# vga3.net
KiCad netlist of a schematic drawn in EAGLE
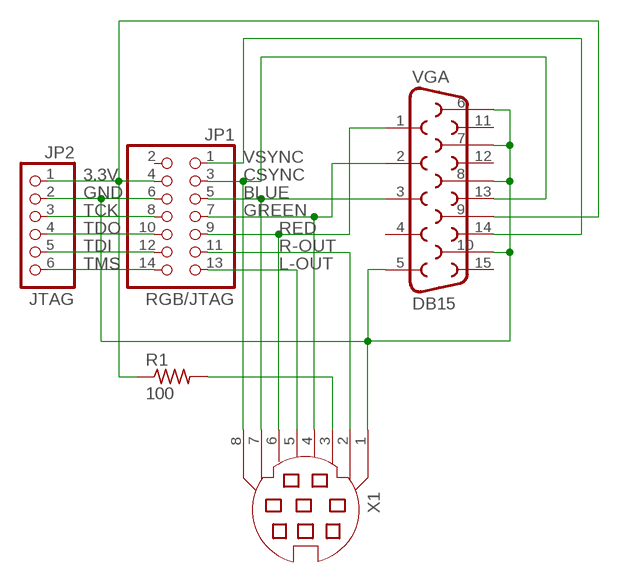
[diagram p0: schematic, sheet 1]

(export (version "E")
  (design (tool "Eeschema 10.0.6"))
  (components
    (comp (ref "JP1")
      (value "RGB/JTAG")
      (footprint "eagle-import:2X07")
      (libsource (lib "eagle-import") (part "PINHD-2X7"))
    )
    (comp (ref "JP2")
      (value "JTAG")
      (footprint "eagle-import:1X06")
      (libsource (lib "eagle-import") (part "PINHD-1X6"))
    )
    (comp (ref "R1")
      (value "100")
      (footprint "eagle-import:0204_7")
      (libsource (lib "eagle-import") (part "R-US_0204/7"))
    )
    (comp (ref "VGA")
      (value "DB15")
      (footprint "eagle-import:DB15")
      (libsource (lib "eagle-import") (part "DB15"))
    )
    (comp (ref "X1")
      (value "MD08S")
      (footprint "eagle-import:MDIN08S")
      (libsource (lib "eagle-import") (part "MD08S"))
    )
  )
  (nets
    (net (code "1") (name "/3.3V") (class "Default")
      (node (ref "JP1") (pin "4") (pinfunction "4_4") (pintype "passive"))
      (node (ref "JP2") (pin "1") (pinfunction "1_1") (pintype "passive"))
      (node (ref "R1") (pin "1") (pinfunction "1_1") (pintype "passive"))
      (node (ref "VGA") (pin "9") (pinfunction "9_9") (pintype "passive"))
    )
    (net (code "2") (name "/BLUE") (class "Default")
      (node (ref "JP1") (pin "5") (pinfunction "5_5") (pintype "passive"))
      (node (ref "VGA") (pin "3") (pinfunction "3_3") (pintype "passive"))
      (node (ref "X1") (pin "7") (pinfunction "7_7") (pintype "passive"))
    )
    (net (code "3") (name "/CSYNC") (class "Default")
      (node (ref "JP1") (pin "3") (pinfunction "3_3") (pintype "passive"))
      (node (ref "VGA") (pin "13") (pinfunction "13_13") (pintype "passive"))
      (node (ref "X1") (pin "8") (pinfunction "8_8") (pintype "passive"))
    )
    (net (code "4") (name "/GND") (class "Default")
      (node (ref "JP1") (pin "6") (pinfunction "6_6") (pintype "passive"))
      (node (ref "JP2") (pin "2") (pinfunction "2_2") (pintype "passive"))
      (node (ref "VGA") (pin "10") (pinfunction "10_10") (pintype "passive"))
      (node (ref "VGA") (pin "5") (pinfunction "5_5") (pintype "passive"))
      (node (ref "VGA") (pin "6") (pinfunction "6_6") (pintype "passive"))
      (node (ref "VGA") (pin "7") (pinfunction "7_7") (pintype "passive"))
      (node (ref "VGA") (pin "8") (pinfunction "8_8") (pintype "passive"))
      (node (ref "X1") (pin "1") (pinfunction "1_1") (pintype "passive"))
    )
    (net (code "5") (name "/GREEN") (class "Default")
      (node (ref "JP1") (pin "7") (pinfunction "7_7") (pintype "passive"))
      (node (ref "VGA") (pin "2") (pinfunction "2_2") (pintype "passive"))
      (node (ref "X1") (pin "4") (pinfunction "4_4") (pintype "passive"))
    )
    (net (code "6") (name "/L-OUT") (class "Default")
      (node (ref "JP1") (pin "13") (pinfunction "13_13") (pintype "passive"))
      (node (ref "X1") (pin "5") (pinfunction "5_5") (pintype "passive"))
    )
    (net (code "7") (name "/R-OUT") (class "Default")
      (node (ref "JP1") (pin "11") (pinfunction "11_11") (pintype "passive"))
      (node (ref "X1") (pin "2") (pinfunction "2_2") (pintype "passive"))
    )
    (net (code "8") (name "/RED") (class "Default")
      (node (ref "JP1") (pin "9") (pinfunction "9_9") (pintype "passive"))
      (node (ref "VGA") (pin "1") (pinfunction "1_1") (pintype "passive"))
      (node (ref "X1") (pin "6") (pinfunction "6_6") (pintype "passive"))
    )
    (net (code "9") (name "/TCK") (class "Default")
      (node (ref "JP1") (pin "8") (pinfunction "8_8") (pintype "passive"))
      (node (ref "JP2") (pin "3") (pinfunction "3_3") (pintype "passive"))
    )
    (net (code "10") (name "/TDI") (class "Default")
      (node (ref "JP1") (pin "12") (pinfunction "12_12") (pintype "passive"))
      (node (ref "JP2") (pin "5") (pinfunction "5_5") (pintype "passive"))
    )
    (net (code "11") (name "/TDO") (class "Default")
      (node (ref "JP1") (pin "10") (pinfunction "10_10") (pintype "passive"))
      (node (ref "JP2") (pin "4") (pinfunction "4_4") (pintype "passive"))
    )
    (net (code "12") (name "/TMS") (class "Default")
      (node (ref "JP1") (pin "14") (pinfunction "14_14") (pintype "passive"))
      (node (ref "JP2") (pin "6") (pinfunction "6_6") (pintype "passive"))
    )
    (net (code "13") (name "/VSYNC") (class "Default")
      (node (ref "JP1") (pin "1") (pinfunction "1_1") (pintype "passive"))
      (node (ref "VGA") (pin "14") (pinfunction "14_14") (pintype "passive"))
    )
    (net (code "14") (name "Net-(R1-Pad2)") (class "Default")
      (node (ref "R1") (pin "2") (pinfunction "2_2") (pintype "passive"))
      (node (ref "X1") (pin "3") (pinfunction "3_3") (pintype "passive"))
    )
    (net (code "15") (name "unconnected-(JP1-Pad2)") (class "Default")
      (node (ref "JP1") (pin "2") (pinfunction "2_2") (pintype "passive"))
    )
    (net (code "16") (name "unconnected-(VGA-Pad4)") (class "Default")
      (node (ref "VGA") (pin "4") (pinfunction "4_4") (pintype "passive"))
    )
    (net (code "17") (name "unconnected-(VGA-Pad11)") (class "Default")
      (node (ref "VGA") (pin "11") (pinfunction "11_11") (pintype "passive"))
    )
    (net (code "18") (name "unconnected-(VGA-Pad12)") (class "Default")
      (node (ref "VGA") (pin "12") (pinfunction "12_12") (pintype "passive"))
    )
    (net (code "19") (name "unconnected-(VGA-Pad15)") (class "Default")
      (node (ref "VGA") (pin "15") (pinfunction "15_15") (pintype "passive"))
    )
  )
)
